# z21_2020_3.net
KiCad netlist of a schematic drawn in EAGLE
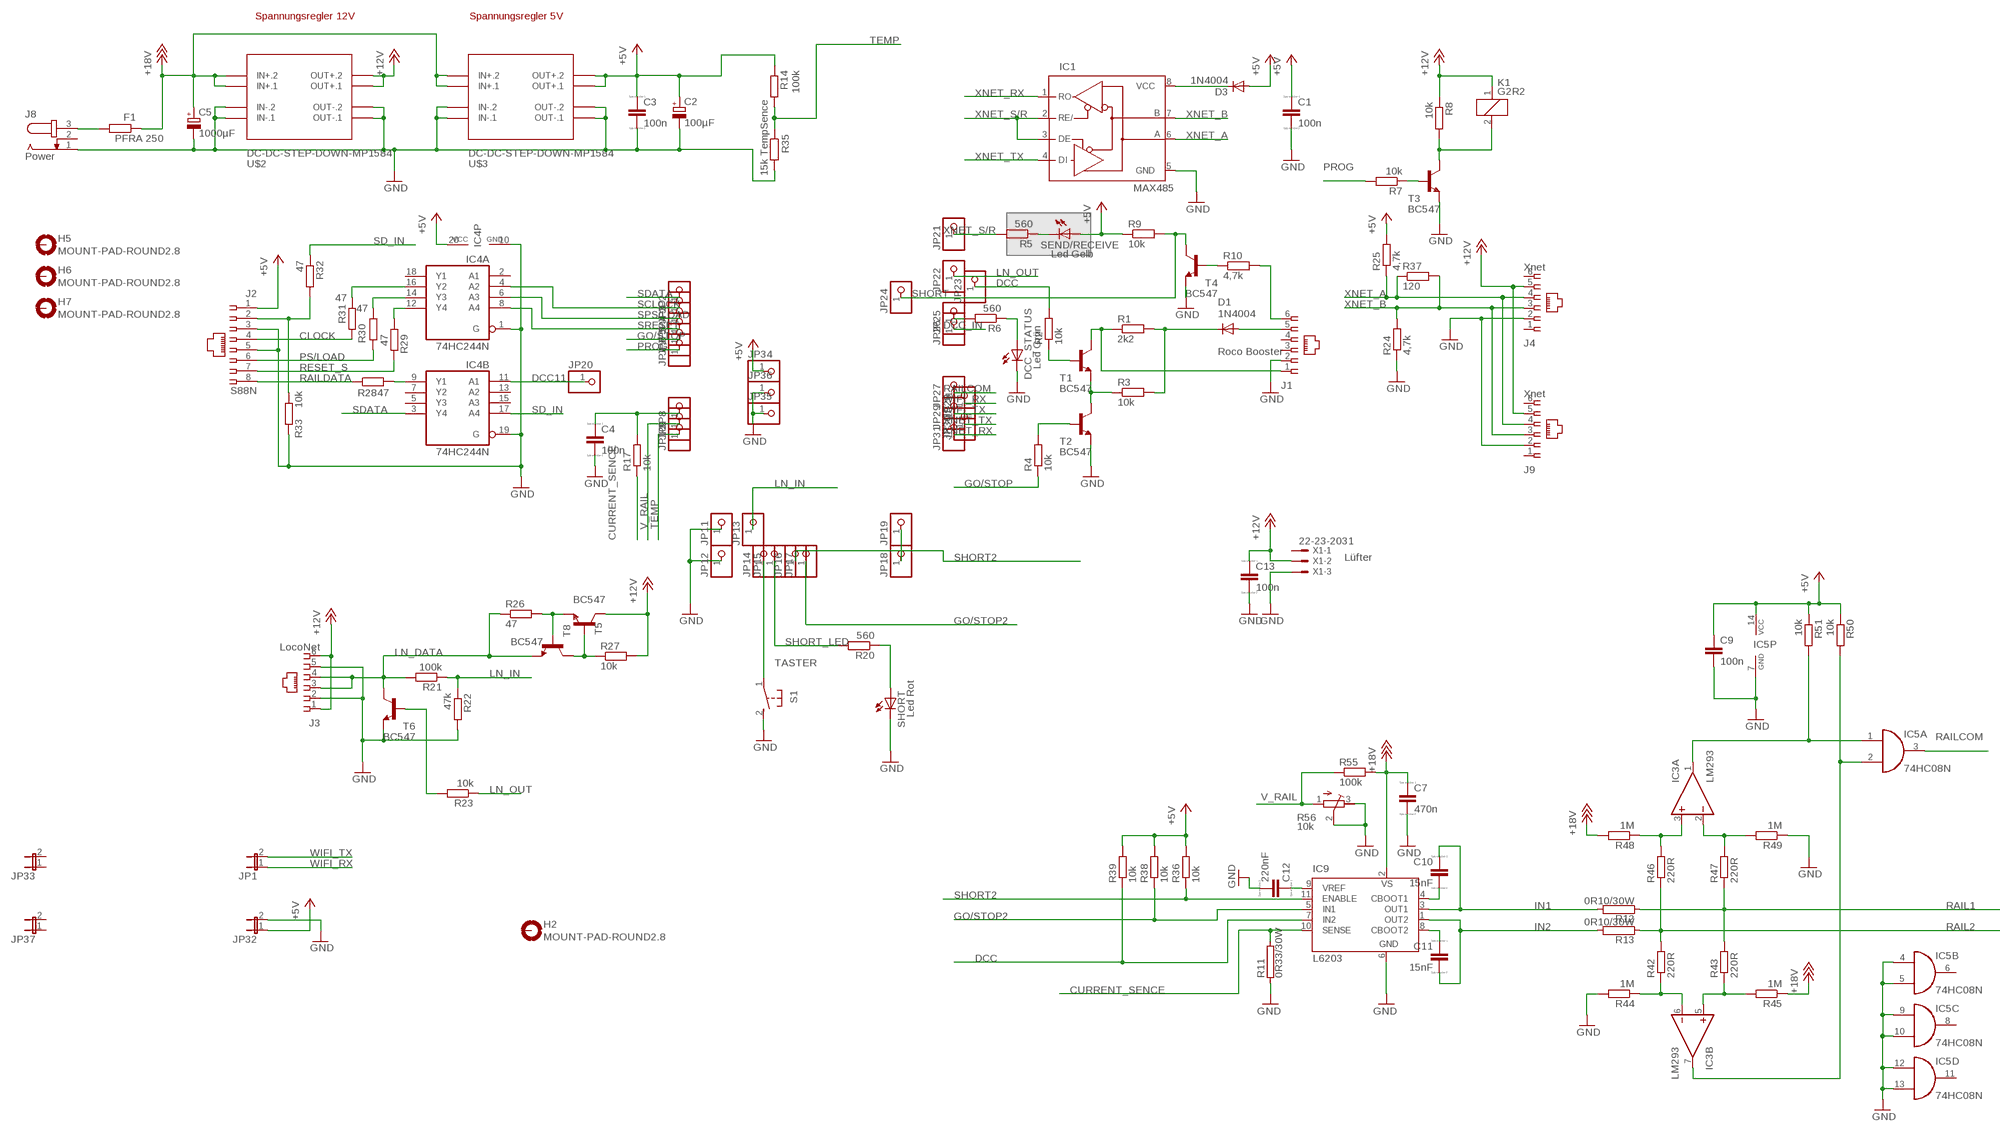
[diagram p0: schematic, sheet 1, part 1 of 2]
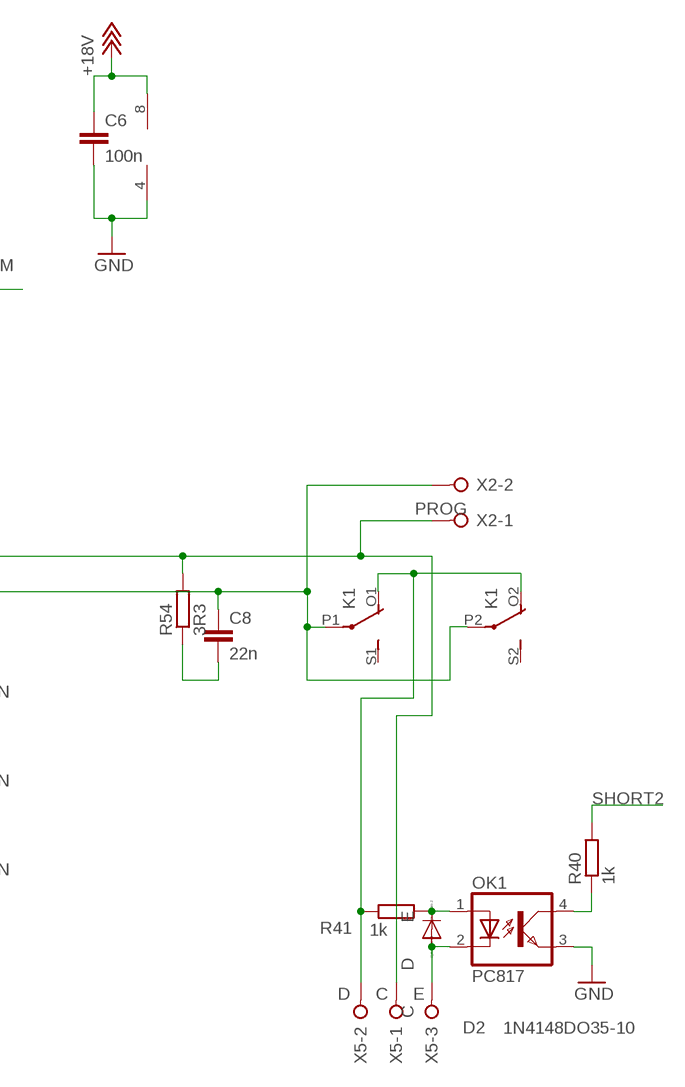
[diagram p1: schematic, sheet 1, part 2 of 2]

(export (version "E")
  (design (tool "Eeschema 10.0.6"))
  (components
    (comp (ref "C1")
      (value "100n")
      (footprint "eagle-import:C050-024X044")
      (libsource (lib "eagle-import") (part "resistor_C-EU050-024X044"))
    )
    (comp (ref "C2")
      (value "100µF")
      (footprint "eagle-import:E3,5-10")
      (libsource (lib "eagle-import") (part "CPOL-EUE3.5-10"))
    )
    (comp (ref "C3")
      (value "100n")
      (footprint "eagle-import:C050-024X044")
      (libsource (lib "eagle-import") (part "resistor_C-EU050-024X044"))
    )
    (comp (ref "C4")
      (value "100n")
      (footprint "eagle-import:C050-024X044")
      (libsource (lib "eagle-import") (part "resistor_C-EU050-024X044"))
    )
    (comp (ref "C5")
      (value "1000µF")
      (footprint "eagle-import:E5-13")
      (libsource (lib "eagle-import") (part "CPOL-EUE5-13"))
    )
    (comp (ref "C6")
      (value "100n")
      (footprint "eagle-import:C050-024X044")
      (libsource (lib "eagle-import") (part "C-EU050-024X044"))
    )
    (comp (ref "C7")
      (value "470n")
      (footprint "eagle-import:C050-024X044")
      (libsource (lib "eagle-import") (part "resistor_C-EU050-024X044"))
    )
    (comp (ref "C8")
      (value "22n")
      (footprint "eagle-import:C050-024X044")
      (libsource (lib "eagle-import") (part "C-EU050-024X044"))
    )
    (comp (ref "C9")
      (value "100n")
      (footprint "eagle-import:C050-024X044")
      (libsource (lib "eagle-import") (part "C-EU050-024X044"))
    )
    (comp (ref "C10")
      (value "15nF")
      (footprint "eagle-import:C050-025X075")
      (libsource (lib "eagle-import") (part "resistor_C-EU050-025X075"))
    )
    (comp (ref "C11")
      (value "15nF")
      (footprint "eagle-import:C050-025X075")
      (libsource (lib "eagle-import") (part "resistor_C-EU050-025X075"))
    )
    (comp (ref "C12")
      (value "220nF")
      (footprint "eagle-import:C050-025X075")
      (libsource (lib "eagle-import") (part "resistor_C-EU050-025X075"))
    )
    (comp (ref "C13")
      (value "100n")
      (footprint "eagle-import:C050-024X044")
      (libsource (lib "eagle-import") (part "resistor_C-EU050-024X044"))
    )
    (comp (ref "D1")
      (value "1N4004")
      (footprint "eagle-import:DO41-10")
      (libsource (lib "eagle-import") (part "1N4004"))
    )
    (comp (ref "D2")
      (value "1N4148DO35-10")
      (footprint "eagle-import:DO35-10")
      (libsource (lib "eagle-import") (part "1N4148DO35-10"))
    )
    (comp (ref "D3")
      (value "1N4004")
      (footprint "eagle-import:DO41-10")
      (libsource (lib "eagle-import") (part "1N4004"))
    )
    (comp (ref "DCC_STATUS")
      (value "Led Grün")
      (footprint "eagle-import:LD260")
      (libsource (lib "eagle-import") (part "LEDLD260"))
    )
    (comp (ref "F1")
      (value "PFRA 250")
      (footprint "eagle-import:0204_5")
      (libsource (lib "eagle-import") (part "R-EU_0204/5"))
    )
    (comp (ref "H2")
      (value "MOUNT-PAD-ROUND2.8")
      (footprint "eagle-import:2,8-PAD")
      (libsource (lib "eagle-import") (part "MOUNT-PAD-ROUND2.8"))
    )
    (comp (ref "H5")
      (value "MOUNT-PAD-ROUND2.8")
      (footprint "eagle-import:2,8-PAD")
      (libsource (lib "eagle-import") (part "MOUNT-PAD-ROUND2.8"))
    )
    (comp (ref "H6")
      (value "MOUNT-PAD-ROUND2.8")
      (footprint "eagle-import:2,8-PAD")
      (libsource (lib "eagle-import") (part "MOUNT-PAD-ROUND2.8"))
    )
    (comp (ref "H7")
      (value "MOUNT-PAD-ROUND2.8")
      (footprint "eagle-import:2,8-PAD")
      (libsource (lib "eagle-import") (part "MOUNT-PAD-ROUND2.8"))
    )
    (comp (ref "IC1")
      (value "MAX485")
      (footprint "eagle-import:DIL08")
      (libsource (lib "eagle-import") (part "MAX34PA68C"))
    )
    (comp (ref "IC3")
      (value "LM293")
      (footprint "eagle-import:DIL08")
      (libsource (lib "eagle-import") (part "LM393N"))
    )
    (comp (ref "IC4")
      (value "74HC244N")
      (footprint "eagle-import:DIL20")
      (libsource (lib "eagle-import") (part "74244NHC"))
    )
    (comp (ref "IC5")
      (value "74HC08N")
      (footprint "eagle-import:DIL14")
      (libsource (lib "eagle-import") (part "7408NHC"))
    )
    (comp (ref "IC9")
      (value "L6203")
      (footprint "eagle-import:MULTIWATT-11")
      (libsource (lib "eagle-import") (part "L6203"))
    )
    (comp (ref "J1")
      (value "Roco Booster")
      (footprint "eagle-import:520250-3")
      (libsource (lib "eagle-import") (part "520250-3"))
    )
    (comp (ref "J2")
      (value "S88N")
      (footprint "eagle-import:520251-4")
      (libsource (lib "eagle-import") (part "520251-4"))
    )
    (comp (ref "J3")
      (value "LocoNet")
      (footprint "eagle-import:520250-3")
      (libsource (lib "eagle-import") (part "520250-3"))
    )
    (comp (ref "J4")
      (value "Xnet")
      (footprint "eagle-import:520250-3")
      (libsource (lib "eagle-import") (part "520250-3"))
    )
    (comp (ref "J8")
      (value "Power")
      (footprint "eagle-import:SPC4077")
      (libsource (lib "eagle-import") (part "JACK-PLUG0"))
    )
    (comp (ref "J9")
      (value "Xnet")
      (footprint "eagle-import:520250-3")
      (libsource (lib "eagle-import") (part "520250-3"))
    )
    (comp (ref "JP1")
      (value "JP1E")
      (footprint "eagle-import:JP1")
      (libsource (lib "eagle-import") (part "JP1E"))
    )
    (comp (ref "JP2")
      (value "PINHD-1X1")
      (footprint "eagle-import:1X01")
      (libsource (lib "eagle-import") (part "PINHD-1X1"))
    )
    (comp (ref "JP3")
      (value "PINHD-1X1")
      (footprint "eagle-import:1X01")
      (libsource (lib "eagle-import") (part "PINHD-1X1"))
    )
    (comp (ref "JP4")
      (value "PINHD-1X1")
      (footprint "eagle-import:1X01")
      (libsource (lib "eagle-import") (part "PINHD-1X1"))
    )
    (comp (ref "JP5")
      (value "PINHD-1X1")
      (footprint "eagle-import:1X01")
      (libsource (lib "eagle-import") (part "PINHD-1X1"))
    )
    (comp (ref "JP6")
      (value "PINHD-1X1")
      (footprint "eagle-import:1X01")
      (libsource (lib "eagle-import") (part "PINHD-1X1"))
    )
    (comp (ref "JP7")
      (value "PINHD-1X1")
      (footprint "eagle-import:1X01")
      (libsource (lib "eagle-import") (part "PINHD-1X1"))
    )
    (comp (ref "JP8")
      (value "PINHD-1X1")
      (footprint "eagle-import:1X01")
      (libsource (lib "eagle-import") (part "PINHD-1X1"))
    )
    (comp (ref "JP9")
      (value "PINHD-1X1")
      (footprint "eagle-import:1X01")
      (libsource (lib "eagle-import") (part "PINHD-1X1"))
    )
    (comp (ref "JP10")
      (value "PINHD-1X1")
      (footprint "eagle-import:1X01")
      (libsource (lib "eagle-import") (part "PINHD-1X1"))
    )
    (comp (ref "JP11")
      (value "PINHD-1X1")
      (footprint "eagle-import:1X01")
      (libsource (lib "eagle-import") (part "PINHD-1X1"))
    )
    (comp (ref "JP12")
      (value "PINHD-1X1")
      (footprint "eagle-import:1X01")
      (libsource (lib "eagle-import") (part "PINHD-1X1"))
    )
    (comp (ref "JP13")
      (value "PINHD-1X1")
      (footprint "eagle-import:1X01")
      (libsource (lib "eagle-import") (part "PINHD-1X1"))
    )
    (comp (ref "JP14")
      (value "PINHD-1X1")
      (footprint "eagle-import:1X01")
      (libsource (lib "eagle-import") (part "PINHD-1X1"))
    )
    (comp (ref "JP15")
      (value "PINHD-1X1")
      (footprint "eagle-import:1X01")
      (libsource (lib "eagle-import") (part "PINHD-1X1"))
    )
    (comp (ref "JP16")
      (value "PINHD-1X1")
      (footprint "eagle-import:1X01")
      (libsource (lib "eagle-import") (part "PINHD-1X1"))
    )
    (comp (ref "JP17")
      (value "PINHD-1X1")
      (footprint "eagle-import:1X01")
      (libsource (lib "eagle-import") (part "PINHD-1X1"))
    )
    (comp (ref "JP18")
      (value "PINHD-1X1")
      (footprint "eagle-import:1X01")
      (libsource (lib "eagle-import") (part "PINHD-1X1"))
    )
    (comp (ref "JP19")
      (value "PINHD-1X1")
      (footprint "eagle-import:1X01")
      (libsource (lib "eagle-import") (part "PINHD-1X1"))
    )
    (comp (ref "JP20")
      (value "PINHD-1X1")
      (footprint "eagle-import:1X01")
      (libsource (lib "eagle-import") (part "PINHD-1X1"))
    )
    (comp (ref "JP21")
      (value "PINHD-1X1")
      (footprint "eagle-import:1X01")
      (libsource (lib "eagle-import") (part "PINHD-1X1"))
    )
    (comp (ref "JP22")
      (value "PINHD-1X1")
      (footprint "eagle-import:1X01")
      (libsource (lib "eagle-import") (part "PINHD-1X1"))
    )
    (comp (ref "JP23")
      (value "PINHD-1X1")
      (footprint "eagle-import:1X01")
      (libsource (lib "eagle-import") (part "PINHD-1X1"))
    )
    (comp (ref "JP24")
      (value "PINHD-1X1")
      (footprint "eagle-import:1X01")
      (libsource (lib "eagle-import") (part "PINHD-1X1"))
    )
    (comp (ref "JP25")
      (value "PINHD-1X1")
      (footprint "eagle-import:1X01")
      (libsource (lib "eagle-import") (part "PINHD-1X1"))
    )
    (comp (ref "JP26")
      (value "PINHD-1X1")
      (footprint "eagle-import:1X01")
      (libsource (lib "eagle-import") (part "PINHD-1X1"))
    )
    (comp (ref "JP27")
      (value "PINHD-1X1")
      (footprint "eagle-import:1X01")
      (libsource (lib "eagle-import") (part "PINHD-1X1"))
    )
    (comp (ref "JP28")
      (value "PINHD-1X1")
      (footprint "eagle-import:1X01")
      (libsource (lib "eagle-import") (part "PINHD-1X1"))
    )
    (comp (ref "JP29")
      (value "PINHD-1X1")
      (footprint "eagle-import:1X01")
      (libsource (lib "eagle-import") (part "PINHD-1X1"))
    )
    (comp (ref "JP30")
      (value "PINHD-1X1")
      (footprint "eagle-import:1X01")
      (libsource (lib "eagle-import") (part "PINHD-1X1"))
    )
    (comp (ref "JP31")
      (value "PINHD-1X1")
      (footprint "eagle-import:1X01")
      (libsource (lib "eagle-import") (part "PINHD-1X1"))
    )
    (comp (ref "JP32")
      (value "JP1E")
      (footprint "eagle-import:JP1")
      (libsource (lib "eagle-import") (part "JP1E"))
    )
    (comp (ref "JP33")
      (value "JP1E")
      (footprint "eagle-import:JP1")
      (libsource (lib "eagle-import") (part "JP1E"))
    )
    (comp (ref "JP34")
      (value "PINHD-1X1")
      (footprint "eagle-import:1X01")
      (libsource (lib "eagle-import") (part "PINHD-1X1"))
    )
    (comp (ref "JP35")
      (value "PINHD-1X1")
      (footprint "eagle-import:1X01")
      (libsource (lib "eagle-import") (part "PINHD-1X1"))
    )
    (comp (ref "JP36")
      (value "PINHD-1X1")
      (footprint "eagle-import:1X01")
      (libsource (lib "eagle-import") (part "PINHD-1X1"))
    )
    (comp (ref "JP37")
      (value "JP1E")
      (footprint "eagle-import:JP1")
      (libsource (lib "eagle-import") (part "JP1E"))
    )
    (comp (ref "K1")
      (value "G2R2")
      (footprint "eagle-import:G2R2")
      (fields (field (name "MF") "OMRON COMPONENTS USA") (field (name "MPN") "G2R-2-DC6"))
      (libsource (lib "eagle-import") (part "G2R2"))
    )
    (comp (ref "OK1")
      (value "PC817")
      (footprint "eagle-import:DIL04")
      (fields (field (name "MPN") "PC817X4J000F"))
      (libsource (lib "eagle-import") (part "PC817"))
    )
    (comp (ref "R1")
      (value "2k2")
      (footprint "eagle-import:0204_7")
      (libsource (lib "eagle-import") (part "R-EU_0204/7"))
    )
    (comp (ref "R2")
      (value "10k")
      (footprint "eagle-import:0204_7")
      (libsource (lib "eagle-import") (part "R-EU_0204/7"))
    )
    (comp (ref "R3")
      (value "10k")
      (footprint "eagle-import:0207_10")
      (libsource (lib "eagle-import") (part "R-EU_0207/10"))
    )
    (comp (ref "R4")
      (value "10k")
      (footprint "eagle-import:0207_15")
      (libsource (lib "eagle-import") (part "R-EU_0207/15"))
    )
    (comp (ref "R5")
      (value "560")
      (footprint "eagle-import:0204_7")
      (libsource (lib "eagle-import") (part "R-EU_0204/7"))
    )
    (comp (ref "R6")
      (value "560")
      (footprint "eagle-import:0204_7")
      (libsource (lib "eagle-import") (part "R-EU_0204/7"))
    )
    (comp (ref "R7")
      (value "10k")
      (footprint "eagle-import:0207_10")
      (libsource (lib "eagle-import") (part "R-EU_0207/10"))
    )
    (comp (ref "R8")
      (value "10k")
      (footprint "eagle-import:0207_10")
      (libsource (lib "eagle-import") (part "R-EU_0207/10"))
    )
    (comp (ref "R9")
      (value "10k")
      (footprint "eagle-import:0207_10")
      (libsource (lib "eagle-import") (part "R-EU_0207/10"))
    )
    (comp (ref "R10")
      (value "4,7k")
      (footprint "eagle-import:0204_7")
      (libsource (lib "eagle-import") (part "R-EU_0204/7"))
    )
    (comp (ref "R11")
      (value "0R33/30W")
      (footprint "eagle-import:MNS-2")
      (libsource (lib "eagle-import") (part "RMNS-2"))
    )
    (comp (ref "R12")
      (value "0R10/30W")
      (footprint "eagle-import:MNS-2")
      (libsource (lib "eagle-import") (part "RMNS-2"))
    )
    (comp (ref "R13")
      (value "0R10/30W")
      (footprint "eagle-import:MNS-2")
      (libsource (lib "eagle-import") (part "RMNS-2"))
    )
    (comp (ref "R14")
      (value "100k")
      (footprint "eagle-import:0207_10")
      (libsource (lib "eagle-import") (part "R-EU_0207/10"))
    )
    (comp (ref "R17")
      (value "10k")
      (footprint "eagle-import:0207_10")
      (libsource (lib "eagle-import") (part "R-EU_0207/10"))
    )
    (comp (ref "R20")
      (value "560")
      (footprint "eagle-import:0204_7")
      (libsource (lib "eagle-import") (part "R-EU_0204/7"))
    )
    (comp (ref "R21")
      (value "100k")
      (footprint "eagle-import:0207_10")
      (libsource (lib "eagle-import") (part "R-EU_0207/10"))
    )
    (comp (ref "R22")
      (value "47k")
      (footprint "eagle-import:0207_10")
      (libsource (lib "eagle-import") (part "R-EU_0207/10"))
    )
    (comp (ref "R23")
      (value "10k")
      (footprint "eagle-import:0207_10")
      (libsource (lib "eagle-import") (part "R-EU_0207/10"))
    )
    (comp (ref "R24")
      (value "4,7k")
      (footprint "eagle-import:0207_10")
      (libsource (lib "eagle-import") (part "R-EU_0207/10"))
    )
    (comp (ref "R25")
      (value "4,7k")
      (footprint "eagle-import:0207_10")
      (libsource (lib "eagle-import") (part "R-EU_0207/10"))
    )
    (comp (ref "R26")
      (value "47")
      (footprint "eagle-import:0204_7")
      (libsource (lib "eagle-import") (part "R-EU_0204/7"))
    )
    (comp (ref "R27")
      (value "10k")
      (footprint "eagle-import:0207_10")
      (libsource (lib "eagle-import") (part "R-EU_0207/10"))
    )
    (comp (ref "R28")
      (value "47")
      (footprint "eagle-import:0207_10")
      (libsource (lib "eagle-import") (part "R-EU_0207/10"))
    )
    (comp (ref "R29")
      (value "47")
      (footprint "eagle-import:0207_10")
      (libsource (lib "eagle-import") (part "R-EU_0207/10"))
    )
    (comp (ref "R30")
      (value "47")
      (footprint "eagle-import:0207_10")
      (libsource (lib "eagle-import") (part "R-EU_0207/10"))
    )
    (comp (ref "R31")
      (value "47")
      (footprint "eagle-import:0207_10")
      (libsource (lib "eagle-import") (part "R-EU_0207/10"))
    )
    (comp (ref "R32")
      (value "47")
      (footprint "eagle-import:0207_10")
      (libsource (lib "eagle-import") (part "R-EU_0207/10"))
    )
    (comp (ref "R33")
      (value "10k")
      (footprint "eagle-import:0207_10")
      (libsource (lib "eagle-import") (part "R-EU_0207/10"))
    )
    (comp (ref "R35")
      (value "15k TempSence")
      (footprint "eagle-import:0204_7")
      (libsource (lib "eagle-import") (part "R-EU_0204/7"))
    )
    (comp (ref "R36")
      (value "10k")
      (footprint "eagle-import:0207_10")
      (libsource (lib "eagle-import") (part "R-EU_0207/10"))
    )
    (comp (ref "R37")
      (value "120")
      (footprint "eagle-import:0207_10")
      (libsource (lib "eagle-import") (part "R-EU_0207/10"))
    )
    (comp (ref "R38")
      (value "10k")
      (footprint "eagle-import:0207_10")
      (libsource (lib "eagle-import") (part "R-EU_0207/10"))
    )
    (comp (ref "R39")
      (value "10k")
      (footprint "eagle-import:0207_10")
      (libsource (lib "eagle-import") (part "R-EU_0207/10"))
    )
    (comp (ref "R40")
      (value "1k")
      (footprint "eagle-import:0207_10")
      (libsource (lib "eagle-import") (part "R-EU_0207/10"))
    )
    (comp (ref "R41")
      (value "1k")
      (footprint "eagle-import:0207_10")
      (libsource (lib "eagle-import") (part "R-EU_0207/10"))
    )
    (comp (ref "R42")
      (value "220R")
      (footprint "eagle-import:0207_10")
      (libsource (lib "eagle-import") (part "resistor_R-EU_0207/10"))
    )
    (comp (ref "R43")
      (value "220R")
      (footprint "eagle-import:0207_10")
      (libsource (lib "eagle-import") (part "resistor_R-EU_0207/10"))
    )
    (comp (ref "R44")
      (value "1M")
      (footprint "eagle-import:0207_10")
      (libsource (lib "eagle-import") (part "resistor_R-EU_0207/10"))
    )
    (comp (ref "R45")
      (value "1M")
      (footprint "eagle-import:0207_10")
      (libsource (lib "eagle-import") (part "resistor_R-EU_0207/10"))
    )
    (comp (ref "R46")
      (value "220R")
      (footprint "eagle-import:0207_10")
      (libsource (lib "eagle-import") (part "resistor_R-EU_0207/10"))
    )
    (comp (ref "R47")
      (value "220R")
      (footprint "eagle-import:0207_10")
      (libsource (lib "eagle-import") (part "resistor_R-EU_0207/10"))
    )
    (comp (ref "R48")
      (value "1M")
      (footprint "eagle-import:0207_10")
      (libsource (lib "eagle-import") (part "resistor_R-EU_0207/10"))
    )
    (comp (ref "R49")
      (value "1M")
      (footprint "eagle-import:0207_10")
      (libsource (lib "eagle-import") (part "resistor_R-EU_0207/10"))
    )
    (comp (ref "R50")
      (value "10k")
      (footprint "eagle-import:0207_10")
      (libsource (lib "eagle-import") (part "resistor_R-EU_0207/10"))
    )
    (comp (ref "R51")
      (value "10k")
      (footprint "eagle-import:0207_10")
      (libsource (lib "eagle-import") (part "resistor_R-EU_0207/10"))
    )
    (comp (ref "R54")
      (value "3R3")
      (footprint "eagle-import:0204_7")
      (libsource (lib "eagle-import") (part "R-EU_0204/7"))
    )
    (comp (ref "R55")
      (value "100k")
      (footprint "eagle-import:0207_12")
      (libsource (lib "eagle-import") (part "R-EU_0207/12"))
    )
    (comp (ref "R56")
      (value "10k")
      (footprint "eagle-import:RTRIM64X")
      (libsource (lib "eagle-import") (part "R-TRIMM64X"))
    )
    (comp (ref "S1")
      (value "31-XX")
      (footprint "eagle-import:B3F-31XX")
      (fields (field (name "MPN") "B3F-3100"))
      (libsource (lib "eagle-import") (part "31-XX"))
    )
    (comp (ref "SEND/RECEIVE")
      (value "Led Gelb")
      (footprint "eagle-import:LD260")
      (libsource (lib "eagle-import") (part "LEDLD260"))
    )
    (comp (ref "SHORT")
      (value "Led Rot")
      (footprint "eagle-import:LD260")
      (libsource (lib "eagle-import") (part "LEDLD260"))
    )
    (comp (ref "T1")
      (value "BC547")
      (footprint "eagle-import:TO92")
      (libsource (lib "eagle-import") (part "BC547"))
    )
    (comp (ref "T2")
      (value "BC547")
      (footprint "eagle-import:TO92")
      (libsource (lib "eagle-import") (part "BC547"))
    )
    (comp (ref "T3")
      (value "BC547")
      (footprint "eagle-import:TO92")
      (libsource (lib "eagle-import") (part "BC547"))
    )
    (comp (ref "T4")
      (value "BC547")
      (footprint "eagle-import:TO92")
      (libsource (lib "eagle-import") (part "BC547"))
    )
    (comp (ref "T5")
      (value "BC547")
      (footprint "eagle-import:TO92")
      (libsource (lib "eagle-import") (part "BC547"))
    )
    (comp (ref "T6")
      (value "BC547")
      (footprint "eagle-import:TO92")
      (libsource (lib "eagle-import") (part "BC547"))
    )
    (comp (ref "T8")
      (value "BC547")
      (footprint "eagle-import:TO92")
      (libsource (lib "eagle-import") (part "BC547"))
    )
    (comp (ref "U$2")
      (value "DC-DC-STEP-DOWN-MP1584")
      (footprint "eagle-import:DC-DC-STEP-DOWN-MP1584")
      (libsource (lib "eagle-import") (part "DC-DC-STEP-DOWN-MP1584"))
    )
    (comp (ref "U$3")
      (value "DC-DC-STEP-DOWN-MP1584")
      (footprint "eagle-import:DC-DC-STEP-DOWN-MP1584")
      (libsource (lib "eagle-import") (part "DC-DC-STEP-DOWN-MP1584"))
    )
    (comp (ref "X1")
      (value "22-23-2031")
      (footprint "eagle-import:22-23-2031")
      (fields (field (name "MF") "MOLEX"))
      (libsource (lib "eagle-import") (part "22-23-2031"))
    )
    (comp (ref "X2")
      (value "PROG")
      (footprint "eagle-import:W237-132")
      (libsource (lib "eagle-import") (part "W237-02P"))
    )
    (comp (ref "X5")
      (value "C D E")
      (footprint "eagle-import:W237-3E")
      (libsource (lib "eagle-import") (part "W237-3E"))
    )
  )
  (nets
    (net (code "1") (name "+5V") (class "Default")
      (node (ref "C1") (pin "1") (pinfunction "1_1") (pintype "passive"))
      (node (ref "C2") (pin "+") (pinfunction "+_+") (pintype "passive"))
      (node (ref "C3") (pin "1") (pinfunction "1_1") (pintype "passive"))
      (node (ref "C9") (pin "1") (pinfunction "1_1") (pintype "passive"))
      (node (ref "D3") (pin "A") (pinfunction "A_A") (pintype "passive"))
      (node (ref "IC4") (pin "20") (pinfunction "VCC_20") (pintype "power_in"))
      (node (ref "IC5") (pin "14") (pinfunction "VCC_14") (pintype "power_in"))
      (node (ref "J2") (pin "1") (pinfunction "1_1") (pintype "passive"))
      (node (ref "JP32") (pin "1") (pinfunction "1_1") (pintype "passive"))
      (node (ref "JP34") (pin "1") (pinfunction "1_1") (pintype "passive"))
      (node (ref "R14") (pin "1") (pinfunction "1_1") (pintype "passive"))
      (node (ref "R25") (pin "2") (pinfunction "2_2") (pintype "passive"))
      (node (ref "R36") (pin "2") (pinfunction "2_2") (pintype "passive"))
      (node (ref "R38") (pin "2") (pinfunction "2_2") (pintype "passive"))
      (node (ref "R39") (pin "2") (pinfunction "2_2") (pintype "passive"))
      (node (ref "R50") (pin "1") (pinfunction "1_1") (pintype "passive"))
      (node (ref "R51") (pin "1") (pinfunction "1_1") (pintype "passive"))
      (node (ref "R9") (pin "1") (pinfunction "1_1") (pintype "passive"))
      (node (ref "SEND/RECEIVE") (pin "A") (pinfunction "A_A") (pintype "passive"))
      (node (ref "U$3") (pin "OUT+.1") (pinfunction "OUT+.1_OUT+.1") (pintype "bidirectional"))
      (node (ref "U$3") (pin "OUT+.2") (pinfunction "OUT+.2_OUT+.2") (pintype "bidirectional"))
    )
    (net (code "2") (name "+12V") (class "Default")
      (node (ref "C13") (pin "1") (pinfunction "1_1") (pintype "passive"))
      (node (ref "J3") (pin "1") (pinfunction "1_1") (pintype "passive"))
      (node (ref "J3") (pin "6") (pinfunction "6_6") (pintype "passive"))
      (node (ref "J4") (pin "5") (pinfunction "5_5") (pintype "passive"))
      (node (ref "J9") (pin "5") (pinfunction "5_5") (pintype "passive"))
      (node (ref "K1") (pin "1") (pinfunction "1_1") (pintype "passive"))
      (node (ref "R27") (pin "2") (pinfunction "2_2") (pintype "passive"))
      (node (ref "R8") (pin "1") (pinfunction "1_1") (pintype "passive"))
      (node (ref "T5") (pin "3") (pinfunction "C_3") (pintype "passive"))
      (node (ref "U$2") (pin "OUT+.1") (pinfunction "OUT+.1_OUT+.1") (pintype "bidirectional"))
      (node (ref "U$2") (pin "OUT+.2") (pinfunction "OUT+.2_OUT+.2") (pintype "bidirectional"))
      (node (ref "X1") (pin "2") (pinfunction "S_2") (pintype "passive"))
    )
    (net (code "3") (name "+18V") (class "Default")
      (node (ref "C5") (pin "+") (pinfunction "+_+") (pintype "passive"))
      (node (ref "C6") (pin "1") (pinfunction "1_1") (pintype "passive"))
      (node (ref "C7") (pin "1") (pinfunction "1_1") (pintype "passive"))
      (node (ref "F1") (pin "1") (pinfunction "1_1") (pintype "passive"))
      (node (ref "IC3") (pin "8") (pinfunction "V+_8") (pintype "power_in"))
      (node (ref "IC9") (pin "2") (pinfunction "VS_2") (pintype "power_in"))
      (node (ref "R45") (pin "1") (pinfunction "1_1") (pintype "passive"))
      (node (ref "R48") (pin "2") (pinfunction "2_2") (pintype "passive"))
      (node (ref "R55") (pin "2") (pinfunction "2_2") (pintype "passive"))
      (node (ref "U$2") (pin "IN+.1") (pinfunction "IN+.1_IN+.1") (pintype "bidirectional"))
      (node (ref "U$2") (pin "IN+.2") (pinfunction "IN+.2_IN+.2") (pintype "bidirectional"))
      (node (ref "U$3") (pin "IN+.1") (pinfunction "IN+.1_IN+.1") (pintype "bidirectional"))
      (node (ref "U$3") (pin "IN+.2") (pinfunction "IN+.2_IN+.2") (pintype "bidirectional"))
    )
    (net (code "4") (name "/CLOCK") (class "Default")
      (node (ref "J2") (pin "4") (pinfunction "4_4") (pintype "passive"))
      (node (ref "R31") (pin "2") (pinfunction "2_2") (pintype "passive"))
    )
    (net (code "5") (name "/CURRENT_SENCE") (class "Default")
      (node (ref "IC9") (pin "10") (pinfunction "SENSE_10") (pintype "input"))
      (node (ref "R11") (pin "2") (pinfunction "2_2") (pintype "passive"))
      (node (ref "R17") (pin "1") (pinfunction "1_1") (pintype "passive"))
    )
    (net (code "6") (name "/DCC") (class "Default")
      (node (ref "IC9") (pin "7") (pinfunction "IN2_7") (pintype "input"))
      (node (ref "JP23") (pin "1") (pinfunction "1_1") (pintype "passive"))
      (node (ref "R2") (pin "2") (pinfunction "2_2") (pintype "passive"))
      (node (ref "R39") (pin "1") (pinfunction "1_1") (pintype "passive"))
    )
    (net (code "7") (name "/DCC11") (class "Default")
      (node (ref "IC4") (pin "11") (pinfunction "A1_11") (pintype "input"))
      (node (ref "JP20") (pin "1") (pinfunction "1_1") (pintype "passive"))
    )
    (net (code "8") (name "/DCC_IN") (class "Default")
      (node (ref "JP26") (pin "1") (pinfunction "1_1") (pintype "passive"))
    )
    (net (code "9") (name "/GO{slash}STOP") (class "Default")
      (node (ref "JP6") (pin "1") (pinfunction "1_1") (pintype "passive"))
      (node (ref "R4") (pin "1") (pinfunction "1_1") (pintype "passive"))
    )
    (net (code "10") (name "/GO{slash}STOP2") (class "Default")
      (node (ref "IC9") (pin "5") (pinfunction "IN1_5") (pintype "input"))
      (node (ref "JP17") (pin "1") (pinfunction "1_1") (pintype "passive"))
      (node (ref "R38") (pin "1") (pinfunction "1_1") (pintype "passive"))
    )
    (net (code "11") (name "/IN1") (class "Default")
      (node (ref "C10") (pin "1") (pinfunction "1_1") (pintype "passive"))
      (node (ref "IC9") (pin "3") (pinfunction "OUT1_3") (pintype "output"))
      (node (ref "R12") (pin "2") (pinfunction "2_2") (pintype "passive"))
    )
    (net (code "12") (name "/IN2") (class "Default")
      (node (ref "C11") (pin "2") (pinfunction "2_2") (pintype "passive"))
      (node (ref "IC9") (pin "1") (pinfunction "OUT2_1") (pintype "output"))
      (node (ref "R13") (pin "2") (pinfunction "2_2") (pintype "passive"))
    )
    (net (code "13") (name "/LN_DATA") (class "Default")
      (node (ref "J3") (pin "3") (pinfunction "3_3") (pintype "passive"))
      (node (ref "J3") (pin "4") (pinfunction "4_4") (pintype "passive"))
      (node (ref "R21") (pin "2") (pinfunction "2_2") (pintype "passive"))
      (node (ref "R26") (pin "1") (pinfunction "1_1") (pintype "passive"))
      (node (ref "T6") (pin "3") (pinfunction "C_3") (pintype "passive"))
      (node (ref "T8") (pin "1") (pinfunction "E_1") (pintype "passive"))
    )
    (net (code "14") (name "/LN_IN") (class "Default")
      (node (ref "JP13") (pin "1") (pinfunction "1_1") (pintype "passive"))
      (node (ref "R21") (pin "1") (pinfunction "1_1") (pintype "passive"))
      (node (ref "R22") (pin "1") (pinfunction "1_1") (pintype "passive"))
    )
    (net (code "15") (name "/LN_OUT") (class "Default")
      (node (ref "JP22") (pin "1") (pinfunction "1_1") (pintype "passive"))
      (node (ref "R23") (pin "1") (pinfunction "1_1") (pintype "passive"))
    )
    (net (code "16") (name "/PROG") (class "Default")
      (node (ref "JP7") (pin "1") (pinfunction "1_1") (pintype "passive"))
      (node (ref "R7") (pin "2") (pinfunction "2_2") (pintype "passive"))
    )
    (net (code "17") (name "/PS{slash}LOAD") (class "Default")
      (node (ref "J2") (pin "6") (pinfunction "6_6") (pintype "passive"))
      (node (ref "R30") (pin "2") (pinfunction "2_2") (pintype "passive"))
    )
    (net (code "18") (name "/RAIL1") (class "Default")
      (node (ref "R12") (pin "1") (pinfunction "1_1") (pintype "passive"))
      (node (ref "R43") (pin "2") (pinfunction "2_2") (pintype "passive"))
      (node (ref "R47") (pin "1") (pinfunction "1_1") (pintype "passive"))
      (node (ref "R54") (pin "2") (pinfunction "2_2") (pintype "passive"))
      (node (ref "X2") (pin "1") (pinfunction "KL_1") (pintype "passive"))
      (node (ref "X5") (pin "1") (pinfunction "KL_1") (pintype "passive"))
    )
    (net (code "19") (name "/RAIL2") (class "Default")
      (node (ref "C8") (pin "1") (pinfunction "1_1") (pintype "passive"))
      (node (ref "K1") (pin "P1") (pinfunction "P_P1") (pintype "passive"))
      (node (ref "K1") (pin "P2") (pinfunction "P_P2") (pintype "passive"))
      (node (ref "R13") (pin "1") (pinfunction "1_1") (pintype "passive"))
      (node (ref "R42") (pin "2") (pinfunction "2_2") (pintype "passive"))
      (node (ref "R46") (pin "1") (pinfunction "1_1") (pintype "passive"))
      (node (ref "X2") (pin "2") (pinfunction "KL_2") (pintype "passive"))
    )
    (net (code "20") (name "/RAILCOM") (class "Default")
      (node (ref "IC5") (pin "3") (pinfunction "O_3") (pintype "output"))
      (node (ref "JP27") (pin "1") (pinfunction "1_1") (pintype "passive"))
    )
    (net (code "21") (name "/RAILDATA") (class "Default")
      (node (ref "J2") (pin "8") (pinfunction "8_8") (pintype "passive"))
      (node (ref "R28") (pin "1") (pinfunction "1_1") (pintype "passive"))
    )
    (net (code "22") (name "/RESET_S") (class "Default")
      (node (ref "J2") (pin "7") (pinfunction "7_7") (pintype "passive"))
      (node (ref "R29") (pin "2") (pinfunction "2_2") (pintype "passive"))
    )
    (net (code "23") (name "/SCLOCK") (class "Default")
      (node (ref "IC4") (pin "4") (pinfunction "A2_4") (pintype "input"))
      (node (ref "JP3") (pin "1") (pinfunction "1_1") (pintype "passive"))
    )
    (net (code "24") (name "/SDATA") (class "Default")
      (node (ref "IC4") (pin "3") (pinfunction "Y4_3") (pintype "tri_state"))
      (node (ref "JP2") (pin "1") (pinfunction "1_1") (pintype "passive"))
    )
    (net (code "25") (name "/SD_IN") (class "Default")
      (node (ref "IC4") (pin "17") (pinfunction "A4_17") (pintype "input"))
      (node (ref "R32") (pin "1") (pinfunction "1_1") (pintype "passive"))
    )
    (net (code "26") (name "/SHORT") (class "Default")
      (node (ref "JP24") (pin "1") (pinfunction "1_1") (pintype "passive"))
      (node (ref "R9") (pin "2") (pinfunction "2_2") (pintype "passive"))
      (node (ref "T4") (pin "3") (pinfunction "C_3") (pintype "passive"))
    )
    (net (code "27") (name "/SHORT2") (class "Default")
      (node (ref "IC9") (pin "11") (pinfunction "ENABLE_11") (pintype "input"))
      (node (ref "JP16") (pin "1") (pinfunction "1_1") (pintype "passive"))
      (node (ref "R36") (pin "1") (pinfunction "1_1") (pintype "passive"))
      (node (ref "R40") (pin "2") (pinfunction "2_2") (pintype "passive"))
    )
    (net (code "28") (name "/SHORT_LED") (class "Default")
      (node (ref "JP15") (pin "1") (pinfunction "1_1") (pintype "passive"))
      (node (ref "R20") (pin "2") (pinfunction "2_2") (pintype "passive"))
    )
    (net (code "29") (name "/SPS{slash}LOAD") (class "Default")
      (node (ref "IC4") (pin "6") (pinfunction "A3_6") (pintype "input"))
      (node (ref "JP4") (pin "1") (pinfunction "1_1") (pintype "passive"))
    )
    (net (code "30") (name "/SRESET") (class "Default")
      (node (ref "IC4") (pin "8") (pinfunction "A4_8") (pintype "input"))
      (node (ref "JP5") (pin "1") (pinfunction "1_1") (pintype "passive"))
    )
    (net (code "31") (name "/TASTER") (class "Default")
      (node (ref "JP14") (pin "1") (pinfunction "1_1") (pintype "passive"))
      (node (ref "S1") (pin "1") (pinfunction "P_1") (pintype "passive"))
    )
    (net (code "32") (name "/TEMP") (class "Default")
      (node (ref "JP10") (pin "1") (pinfunction "1_1") (pintype "passive"))
      (node (ref "R14") (pin "2") (pinfunction "2_2") (pintype "passive"))
      (node (ref "R35") (pin "1") (pinfunction "1_1") (pintype "passive"))
    )
    (net (code "33") (name "/V_RAIL") (class "Default")
      (node (ref "JP9") (pin "1") (pinfunction "1_1") (pintype "passive"))
      (node (ref "R55") (pin "1") (pinfunction "1_1") (pintype "passive"))
      (node (ref "R56") (pin "1") (pinfunction "A_1") (pintype "passive"))
    )
    (net (code "34") (name "/WIFI_RX") (class "Default")
      (node (ref "JP1") (pin "1") (pinfunction "1_1") (pintype "passive"))
      (node (ref "JP28") (pin "1") (pinfunction "1_1") (pintype "passive"))
    )
    (net (code "35") (name "/WIFI_TX") (class "Default")
      (node (ref "JP1") (pin "2") (pinfunction "2_2") (pintype "passive"))
      (node (ref "JP29") (pin "1") (pinfunction "1_1") (pintype "passive"))
    )
    (net (code "36") (name "/XNET_A") (class "Default")
      (node (ref "IC1") (pin "6") (pinfunction "A_6") (pintype "passive"))
      (node (ref "J4") (pin "4") (pinfunction "4_4") (pintype "passive"))
      (node (ref "J9") (pin "4") (pinfunction "4_4") (pintype "passive"))
      (node (ref "R25") (pin "1") (pinfunction "1_1") (pintype "passive"))
      (node (ref "R37") (pin "1") (pinfunction "1_1") (pintype "passive"))
    )
    (net (code "37") (name "/XNET_B") (class "Default")
      (node (ref "IC1") (pin "7") (pinfunction "B_7") (pintype "passive"))
      (node (ref "J4") (pin "3") (pinfunction "3_3") (pintype "passive"))
      (node (ref "J9") (pin "3") (pinfunction "3_3") (pintype "passive"))
      (node (ref "R24") (pin "2") (pinfunction "2_2") (pintype "passive"))
      (node (ref "R37") (pin "2") (pinfunction "2_2") (pintype "passive"))
    )
    (net (code "38") (name "/XNET_RX") (class "Default")
      (node (ref "IC1") (pin "1") (pinfunction "RO_1") (pintype "output"))
      (node (ref "JP31") (pin "1") (pinfunction "1_1") (pintype "passive"))
    )
    (net (code "39") (name "/XNET_S{slash}R") (class "Default")
      (node (ref "IC1") (pin "2") (pinfunction "RE/_2") (pintype "input"))
      (node (ref "IC1") (pin "3") (pinfunction "DE_3") (pintype "input"))
      (node (ref "JP21") (pin "1") (pinfunction "1_1") (pintype "passive"))
      (node (ref "R5") (pin "2") (pinfunction "2_2") (pintype "passive"))
    )
    (net (code "40") (name "/XNET_TX") (class "Default")
      (node (ref "IC1") (pin "4") (pinfunction "DI_4") (pintype "input"))
      (node (ref "JP30") (pin "1") (pinfunction "1_1") (pintype "passive"))
    )
    (net (code "41") (name "GND") (class "Default")
      (node (ref "C1") (pin "2") (pinfunction "2_2") (pintype "passive"))
      (node (ref "C12") (pin "2") (pinfunction "2_2") (pintype "passive"))
      (node (ref "C13") (pin "2") (pinfunction "2_2") (pintype "passive"))
      (node (ref "C2") (pin "-") (pinfunction "-_-") (pintype "passive"))
      (node (ref "C3") (pin "2") (pinfunction "2_2") (pintype "passive"))
      (node (ref "C4") (pin "2") (pinfunction "2_2") (pintype "passive"))
      (node (ref "C5") (pin "-") (pinfunction "-_-") (pintype "passive"))
      (node (ref "C6") (pin "2") (pinfunction "2_2") (pintype "passive"))
      (node (ref "C7") (pin "2") (pinfunction "2_2") (pintype "passive"))
      (node (ref "C9") (pin "2") (pinfunction "2_2") (pintype "passive"))
      (node (ref "DCC_STATUS") (pin "K") (pinfunction "C_K") (pintype "passive"))
      (node (ref "IC1") (pin "5") (pinfunction "GND_5") (pintype "power_in"))
      (node (ref "IC3") (pin "4") (pinfunction "V-_4") (pintype "power_in"))
      (node (ref "IC4") (pin "1") (pinfunction "G_1") (pintype "input"))
      (node (ref "IC4") (pin "10") (pinfunction "GND_10") (pintype "power_in"))
      (node (ref "IC4") (pin "19") (pinfunction "G_19") (pintype "input"))
      (node (ref "IC5") (pin "10") (pinfunction "I1_10") (pintype "input"))
      (node (ref "IC5") (pin "12") (pinfunction "I0_12") (pintype "input"))
      (node (ref "IC5") (pin "13") (pinfunction "I1_13") (pintype "input"))
      (node (ref "IC5") (pin "4") (pinfunction "I0_4") (pintype "input"))
      (node (ref "IC5") (pin "5") (pinfunction "I1_5") (pintype "input"))
      (node (ref "IC5") (pin "7") (pinfunction "GND_7") (pintype "power_in"))
      (node (ref "IC5") (pin "9") (pinfunction "I0_9") (pintype "input"))
      (node (ref "IC9") (pin "6") (pinfunction "GND_6") (pintype "power_in"))
      (node (ref "J1") (pin "2") (pinfunction "2_2") (pintype "passive"))
      (node (ref "J2") (pin "3") (pinfunction "3_3") (pintype "passive"))
      (node (ref "J2") (pin "5") (pinfunction "5_5") (pintype "passive"))
      (node (ref "J3") (pin "2") (pinfunction "2_2") (pintype "passive"))
      (node (ref "J3") (pin "5") (pinfunction "5_5") (pintype "passive"))
      (node (ref "J4") (pin "2") (pinfunction "2_2") (pintype "passive"))
      (node (ref "J8") (pin "1") (pinfunction "1_1") (pintype "passive"))
      (node (ref "J9") (pin "2") (pinfunction "2_2") (pintype "passive"))
      (node (ref "JP11") (pin "1") (pinfunction "1_1") (pintype "passive"))
      (node (ref "JP12") (pin "1") (pinfunction "1_1") (pintype "passive"))
      (node (ref "JP32") (pin "2") (pinfunction "2_2") (pintype "passive"))
      (node (ref "JP35") (pin "1") (pinfunction "1_1") (pintype "passive"))
      (node (ref "JP36") (pin "1") (pinfunction "1_1") (pintype "passive"))
      (node (ref "OK1") (pin "3") (pinfunction "EMIT_3") (pintype "passive"))
      (node (ref "R11") (pin "1") (pinfunction "1_1") (pintype "passive"))
      (node (ref "R22") (pin "2") (pinfunction "2_2") (pintype "passive"))
      (node (ref "R24") (pin "1") (pinfunction "1_1") (pintype "passive"))
      (node (ref "R33") (pin "2") (pinfunction "2_2") (pintype "passive"))
      (node (ref "R35") (pin "2") (pinfunction "2_2") (pintype "passive"))
      (node (ref "R44") (pin "2") (pinfunction "2_2") (pintype "passive"))
      (node (ref "R49") (pin "1") (pinfunction "1_1") (pintype "passive"))
      (node (ref "R56") (pin "2") (pinfunction "S_2") (pintype "passive"))
      (node (ref "R56") (pin "3") (pinfunction "E_3") (pintype "passive"))
      (node (ref "S1") (pin "2") (pinfunction "S_2") (pintype "passive"))
      (node (ref "SHORT") (pin "K") (pinfunction "C_K") (pintype "passive"))
      (node (ref "T2") (pin "1") (pinfunction "E_1") (pintype "passive"))
      (node (ref "T3") (pin "1") (pinfunction "E_1") (pintype "passive"))
      (node (ref "T4") (pin "1") (pinfunction "E_1") (pintype "passive"))
      (node (ref "T6") (pin "1") (pinfunction "E_1") (pintype "passive"))
      (node (ref "U$2") (pin "IN-.1") (pinfunction "IN-.1_IN-.1") (pintype "bidirectional"))
      (node (ref "U$2") (pin "IN-.2") (pinfunction "IN-.2_IN-.2") (pintype "bidirectional"))
      (node (ref "U$2") (pin "OUT-.1") (pinfunction "OUT-.1_OUT-.1") (pintype "bidirectional"))
      (node (ref "U$2") (pin "OUT-.2") (pinfunction "OUT-.2_OUT-.2") (pintype "bidirectional"))
      (node (ref "U$3") (pin "IN-.1") (pinfunction "IN-.1_IN-.1") (pintype "bidirectional"))
      (node (ref "U$3") (pin "IN-.2") (pinfunction "IN-.2_IN-.2") (pintype "bidirectional"))
      (node (ref "U$3") (pin "OUT-.1") (pinfunction "OUT-.1_OUT-.1") (pintype "bidirectional"))
      (node (ref "U$3") (pin "OUT-.2") (pinfunction "OUT-.2_OUT-.2") (pintype "bidirectional"))
      (node (ref "X1") (pin "3") (pinfunction "S_3") (pintype "passive"))
    )
    (net (code "42") (name "Net-(C4-Pad1)") (class "Default")
      (node (ref "C4") (pin "1") (pinfunction "1_1") (pintype "passive"))
      (node (ref "JP8") (pin "1") (pinfunction "1_1") (pintype "passive"))
      (node (ref "R17") (pin "2") (pinfunction "2_2") (pintype "passive"))
    )
    (net (code "43") (name "Net-(C8-Pad2)") (class "Default")
      (node (ref "C8") (pin "2") (pinfunction "2_2") (pintype "passive"))
      (node (ref "R54") (pin "1") (pinfunction "1_1") (pintype "passive"))
    )
    (net (code "44") (name "Net-(D1-PadA)") (class "Default")
      (node (ref "D1") (pin "A") (pinfunction "A_A") (pintype "passive"))
      (node (ref "J1") (pin "5") (pinfunction "5_5") (pintype "passive"))
    )
    (net (code "45") (name "Net-(D1-PadC)") (class "Default")
      (node (ref "D1") (pin "C") (pinfunction "C_C") (pintype "passive"))
      (node (ref "R1") (pin "2") (pinfunction "2_2") (pintype "passive"))
      (node (ref "R3") (pin "2") (pinfunction "2_2") (pintype "passive"))
    )
    (net (code "46") (name "Net-(DCC_STATUS-PadA)") (class "Default")
      (node (ref "DCC_STATUS") (pin "A") (pinfunction "A_A") (pintype "passive"))
      (node (ref "R6") (pin "1") (pinfunction "1_1") (pintype "passive"))
    )
    (net (code "47") (name "Net-(F1-Pad2)") (class "Default")
      (node (ref "F1") (pin "2") (pinfunction "2_2") (pintype "passive"))
      (node (ref "J8") (pin "3") (pinfunction "3_3") (pintype "passive"))
    )
    (net (code "48") (name "Net-(IC1-VCC)") (class "Default")
      (node (ref "D3") (pin "C") (pinfunction "C_C") (pintype "passive"))
      (node (ref "IC1") (pin "8") (pinfunction "VCC_8") (pintype "power_in"))
    )
    (net (code "49") (name "Net-(IC3A-+IN)") (class "Default")
      (node (ref "IC3") (pin "3") (pinfunction "+IN_3") (pintype "input"))
      (node (ref "R46") (pin "2") (pinfunction "2_2") (pintype "passive"))
      (node (ref "R48") (pin "1") (pinfunction "1_1") (pintype "passive"))
    )
    (net (code "50") (name "Net-(IC3A--IN)") (class "Default")
      (node (ref "IC3") (pin "2") (pinfunction "-IN_2") (pintype "input"))
      (node (ref "R47") (pin "2") (pinfunction "2_2") (pintype "passive"))
      (node (ref "R49") (pin "2") (pinfunction "2_2") (pintype "passive"))
    )
    (net (code "51") (name "Net-(IC3A-OUT)") (class "Default")
      (node (ref "IC3") (pin "1") (pinfunction "OUT_1") (pintype "output"))
      (node (ref "IC5") (pin "1") (pinfunction "I0_1") (pintype "input"))
      (node (ref "R51") (pin "2") (pinfunction "2_2") (pintype "passive"))
    )
    (net (code "52") (name "Net-(IC3B-+IN)") (class "Default")
      (node (ref "IC3") (pin "5") (pinfunction "+IN_5") (pintype "input"))
      (node (ref "R43") (pin "1") (pinfunction "1_1") (pintype "passive"))
      (node (ref "R45") (pin "2") (pinfunction "2_2") (pintype "passive"))
    )
    (net (code "53") (name "Net-(IC3B--IN)") (class "Default")
      (node (ref "IC3") (pin "6") (pinfunction "-IN_6") (pintype "input"))
      (node (ref "R42") (pin "1") (pinfunction "1_1") (pintype "passive"))
      (node (ref "R44") (pin "1") (pinfunction "1_1") (pintype "passive"))
    )
    (net (code "54") (name "Net-(IC3B-OUT)") (class "Default")
      (node (ref "IC3") (pin "7") (pinfunction "OUT_7") (pintype "output"))
      (node (ref "IC5") (pin "2") (pinfunction "I1_2") (pintype "input"))
      (node (ref "R50") (pin "2") (pinfunction "2_2") (pintype "passive"))
    )
    (net (code "55") (name "Net-(IC4A-Y2)") (class "Default")
      (node (ref "IC4") (pin "16") (pinfunction "Y2_16") (pintype "tri_state"))
      (node (ref "R31") (pin "1") (pinfunction "1_1") (pintype "passive"))
    )
    (net (code "56") (name "Net-(IC4A-Y3)") (class "Default")
      (node (ref "IC4") (pin "14") (pinfunction "Y3_14") (pintype "tri_state"))
      (node (ref "R30") (pin "1") (pinfunction "1_1") (pintype "passive"))
    )
    (net (code "57") (name "Net-(IC4A-Y4)") (class "Default")
      (node (ref "IC4") (pin "12") (pinfunction "Y4_12") (pintype "tri_state"))
      (node (ref "R29") (pin "1") (pinfunction "1_1") (pintype "passive"))
    )
    (net (code "58") (name "Net-(IC4B-Y1)") (class "Default")
      (node (ref "IC4") (pin "9") (pinfunction "Y1_9") (pintype "tri_state"))
      (node (ref "R28") (pin "2") (pinfunction "2_2") (pintype "passive"))
    )
    (net (code "59") (name "Net-(IC9-CBOOT1)") (class "Default")
      (node (ref "C10") (pin "2") (pinfunction "2_2") (pintype "passive"))
      (node (ref "IC9") (pin "4") (pinfunction "CBOOT1_4") (pintype "input"))
    )
    (net (code "60") (name "Net-(IC9-CBOOT2)") (class "Default")
      (node (ref "C11") (pin "1") (pinfunction "1_1") (pintype "passive"))
      (node (ref "IC9") (pin "8") (pinfunction "CBOOT2_8") (pintype "input"))
    )
    (net (code "61") (name "Net-(IC9-VREF)") (class "Default")
      (node (ref "C12") (pin "1") (pinfunction "1_1") (pintype "passive"))
      (node (ref "IC9") (pin "9") (pinfunction "VREF_9") (pintype "input"))
    )
    (net (code "62") (name "Net-(J1-Pad6)") (class "Default")
      (node (ref "J1") (pin "6") (pinfunction "6_6") (pintype "passive"))
      (node (ref "R10") (pin "2") (pinfunction "2_2") (pintype "passive"))
    )
    (net (code "63") (name "Net-(J2-Pad2)") (class "Default")
      (node (ref "J2") (pin "2") (pinfunction "2_2") (pintype "passive"))
      (node (ref "R32") (pin "2") (pinfunction "2_2") (pintype "passive"))
      (node (ref "R33") (pin "1") (pinfunction "1_1") (pintype "passive"))
    )
    (net (code "64") (name "Net-(JP18-Pad1)") (class "Default")
      (node (ref "JP18") (pin "1") (pinfunction "1_1") (pintype "passive"))
      (node (ref "JP19") (pin "1") (pinfunction "1_1") (pintype "passive"))
    )
    (net (code "65") (name "Net-(JP25-Pad1)") (class "Default")
      (node (ref "JP25") (pin "1") (pinfunction "1_1") (pintype "passive"))
      (node (ref "R6") (pin "2") (pinfunction "2_2") (pintype "passive"))
    )
    (net (code "66") (name "Net-(K1B-O)") (class "Default")
      (node (ref "K1") (pin "O1") (pinfunction "O_O1") (pintype "passive"))
      (node (ref "K1") (pin "O2") (pinfunction "O_O2") (pintype "passive"))
      (node (ref "R41") (pin "2") (pinfunction "2_2") (pintype "passive"))
      (node (ref "X5") (pin "2") (pinfunction "KL_2") (pintype "passive"))
    )
    (net (code "67") (name "Net-(OK1-A)") (class "Default")
      (node (ref "D2") (pin "C") (pinfunction "C_C") (pintype "passive"))
      (node (ref "OK1") (pin "1") (pinfunction "A_1") (pintype "passive"))
      (node (ref "R41") (pin "1") (pinfunction "1_1") (pintype "passive"))
    )
    (net (code "68") (name "Net-(OK1-C)") (class "Default")
      (node (ref "D2") (pin "A") (pinfunction "A_A") (pintype "passive"))
      (node (ref "OK1") (pin "2") (pinfunction "C_2") (pintype "passive"))
      (node (ref "X5") (pin "3") (pinfunction "KL_3") (pintype "passive"))
    )
    (net (code "69") (name "Net-(OK1-COL)") (class "Default")
      (node (ref "OK1") (pin "4") (pinfunction "COL_4") (pintype "passive"))
      (node (ref "R40") (pin "1") (pinfunction "1_1") (pintype "passive"))
    )
    (net (code "70") (name "Net-(R20-Pad1)") (class "Default")
      (node (ref "R20") (pin "1") (pinfunction "1_1") (pintype "passive"))
      (node (ref "SHORT") (pin "A") (pinfunction "A_A") (pintype "passive"))
    )
    (net (code "71") (name "Net-(SEND/RECEIVE-C)") (class "Default")
      (node (ref "R5") (pin "1") (pinfunction "1_1") (pintype "passive"))
      (node (ref "SEND/RECEIVE") (pin "K") (pinfunction "C_K") (pintype "passive"))
    )
    (net (code "72") (name "Net-(T1-B)") (class "Default")
      (node (ref "R2") (pin "1") (pinfunction "1_1") (pintype "passive"))
      (node (ref "T1") (pin "2") (pinfunction "B_2") (pintype "passive"))
    )
    (net (code "73") (name "Net-(T1-C)") (class "Default")
      (node (ref "J1") (pin "1") (pinfunction "1_1") (pintype "passive"))
      (node (ref "R1") (pin "1") (pinfunction "1_1") (pintype "passive"))
      (node (ref "T1") (pin "3") (pinfunction "C_3") (pintype "passive"))
    )
    (net (code "74") (name "Net-(T1-E)") (class "Default")
      (node (ref "R3") (pin "1") (pinfunction "1_1") (pintype "passive"))
      (node (ref "T1") (pin "1") (pinfunction "E_1") (pintype "passive"))
      (node (ref "T2") (pin "3") (pinfunction "C_3") (pintype "passive"))
    )
    (net (code "75") (name "Net-(T2-B)") (class "Default")
      (node (ref "R4") (pin "2") (pinfunction "2_2") (pintype "passive"))
      (node (ref "T2") (pin "2") (pinfunction "B_2") (pintype "passive"))
    )
    (net (code "76") (name "Net-(T3-B)") (class "Default")
      (node (ref "R7") (pin "1") (pinfunction "1_1") (pintype "passive"))
      (node (ref "T3") (pin "2") (pinfunction "B_2") (pintype "passive"))
    )
    (net (code "77") (name "Net-(T3-C)") (class "Default")
      (node (ref "K1") (pin "2") (pinfunction "2_2") (pintype "passive"))
      (node (ref "R8") (pin "2") (pinfunction "2_2") (pintype "passive"))
      (node (ref "T3") (pin "3") (pinfunction "C_3") (pintype "passive"))
    )
    (net (code "78") (name "Net-(T4-B)") (class "Default")
      (node (ref "R10") (pin "1") (pinfunction "1_1") (pintype "passive"))
      (node (ref "T4") (pin "2") (pinfunction "B_2") (pintype "passive"))
    )
    (net (code "79") (name "Net-(T5-B)") (class "Default")
      (node (ref "R27") (pin "1") (pinfunction "1_1") (pintype "passive"))
      (node (ref "T5") (pin "2") (pinfunction "B_2") (pintype "passive"))
      (node (ref "T8") (pin "3") (pinfunction "C_3") (pintype "passive"))
    )
    (net (code "80") (name "Net-(T5-E)") (class "Default")
      (node (ref "R26") (pin "2") (pinfunction "2_2") (pintype "passive"))
      (node (ref "T5") (pin "1") (pinfunction "E_1") (pintype "passive"))
      (node (ref "T8") (pin "2") (pinfunction "B_2") (pintype "passive"))
    )
    (net (code "81") (name "Net-(T6-B)") (class "Default")
      (node (ref "R23") (pin "2") (pinfunction "2_2") (pintype "passive"))
      (node (ref "T6") (pin "2") (pinfunction "B_2") (pintype "passive"))
    )
    (net (code "82") (name "unconnected-(H2-MOUNT-PadB2,8)") (class "Default")
      (node (ref "H2") (pin "B2,8") (pinfunction "MOUNT_B2,8") (pintype "passive"))
    )
    (net (code "83") (name "unconnected-(H5-MOUNT-PadB2,8)") (class "Default")
      (node (ref "H5") (pin "B2,8") (pinfunction "MOUNT_B2,8") (pintype "passive"))
    )
    (net (code "84") (name "unconnected-(H6-MOUNT-PadB2,8)") (class "Default")
      (node (ref "H6") (pin "B2,8") (pinfunction "MOUNT_B2,8") (pintype "passive"))
    )
    (net (code "85") (name "unconnected-(H7-MOUNT-PadB2,8)") (class "Default")
      (node (ref "H7") (pin "B2,8") (pinfunction "MOUNT_B2,8") (pintype "passive"))
    )
    (net (code "86") (name "unconnected-(IC4A-A1-Pad2)") (class "Default")
      (node (ref "IC4") (pin "2") (pinfunction "A1_2") (pintype "input"))
    )
    (net (code "87") (name "unconnected-(IC4A-Y1-Pad18)") (class "Default")
      (node (ref "IC4") (pin "18") (pinfunction "Y1_18") (pintype "tri_state"))
    )
    (net (code "88") (name "unconnected-(IC4B-A2-Pad13)") (class "Default")
      (node (ref "IC4") (pin "13") (pinfunction "A2_13") (pintype "input"))
    )
    (net (code "89") (name "unconnected-(IC4B-A3-Pad15)") (class "Default")
      (node (ref "IC4") (pin "15") (pinfunction "A3_15") (pintype "input"))
    )
    (net (code "90") (name "unconnected-(IC4B-Y2-Pad7)") (class "Default")
      (node (ref "IC4") (pin "7") (pinfunction "Y2_7") (pintype "tri_state"))
    )
    (net (code "91") (name "unconnected-(IC4B-Y3-Pad5)") (class "Default")
      (node (ref "IC4") (pin "5") (pinfunction "Y3_5") (pintype "tri_state"))
    )
    (net (code "92") (name "unconnected-(IC5B-O-Pad6)") (class "Default")
      (node (ref "IC5") (pin "6") (pinfunction "O_6") (pintype "output"))
    )
    (net (code "93") (name "unconnected-(IC5C-O-Pad8)") (class "Default")
      (node (ref "IC5") (pin "8") (pinfunction "O_8") (pintype "output"))
    )
    (net (code "94") (name "unconnected-(IC5D-O-Pad11)") (class "Default")
      (node (ref "IC5") (pin "11") (pinfunction "O_11") (pintype "output"))
    )
    (net (code "95") (name "unconnected-(J1-Pad3)") (class "Default")
      (node (ref "J1") (pin "3") (pinfunction "3_3") (pintype "passive"))
    )
    (net (code "96") (name "unconnected-(J1-Pad4)") (class "Default")
      (node (ref "J1") (pin "4") (pinfunction "4_4") (pintype "passive"))
    )
    (net (code "97") (name "unconnected-(J4-Pad1)") (class "Default")
      (node (ref "J4") (pin "1") (pinfunction "1_1") (pintype "passive"))
    )
    (net (code "98") (name "unconnected-(J4-Pad6)") (class "Default")
      (node (ref "J4") (pin "6") (pinfunction "6_6") (pintype "passive"))
    )
    (net (code "99") (name "unconnected-(J8-Pad2)") (class "Default")
      (node (ref "J8") (pin "2") (pinfunction "2_2") (pintype "passive"))
    )
    (net (code "100") (name "unconnected-(J9-Pad1)") (class "Default")
      (node (ref "J9") (pin "1") (pinfunction "1_1") (pintype "passive"))
    )
    (net (code "101") (name "unconnected-(J9-Pad6)") (class "Default")
      (node (ref "J9") (pin "6") (pinfunction "6_6") (pintype "passive"))
    )
    (net (code "102") (name "unconnected-(JP33-Pad1)") (class "Default")
      (node (ref "JP33") (pin "1") (pinfunction "1_1") (pintype "passive"))
    )
    (net (code "103") (name "unconnected-(JP33-Pad2)") (class "Default")
      (node (ref "JP33") (pin "2") (pinfunction "2_2") (pintype "passive"))
    )
    (net (code "104") (name "unconnected-(JP37-Pad1)") (class "Default")
      (node (ref "JP37") (pin "1") (pinfunction "1_1") (pintype "passive"))
    )
    (net (code "105") (name "unconnected-(JP37-Pad2)") (class "Default")
      (node (ref "JP37") (pin "2") (pinfunction "2_2") (pintype "passive"))
    )
    (net (code "106") (name "unconnected-(K1B-S-PadS1)") (class "Default")
      (node (ref "K1") (pin "S1") (pinfunction "S_S1") (pintype "passive"))
    )
    (net (code "107") (name "unconnected-(K1C-S-PadS2)") (class "Default")
      (node (ref "K1") (pin "S2") (pinfunction "S_S2") (pintype "passive"))
    )
    (net (code "108") (name "unconnected-(X1A-S-Pad1)") (class "Default")
      (node (ref "X1") (pin "1") (pinfunction "S_1") (pintype "passive"))
    )
  )
)
